# P23_MIPI_CSI1_MIPI_CSI2.net
KiCad netlist of a schematic drawn in Altium Designer
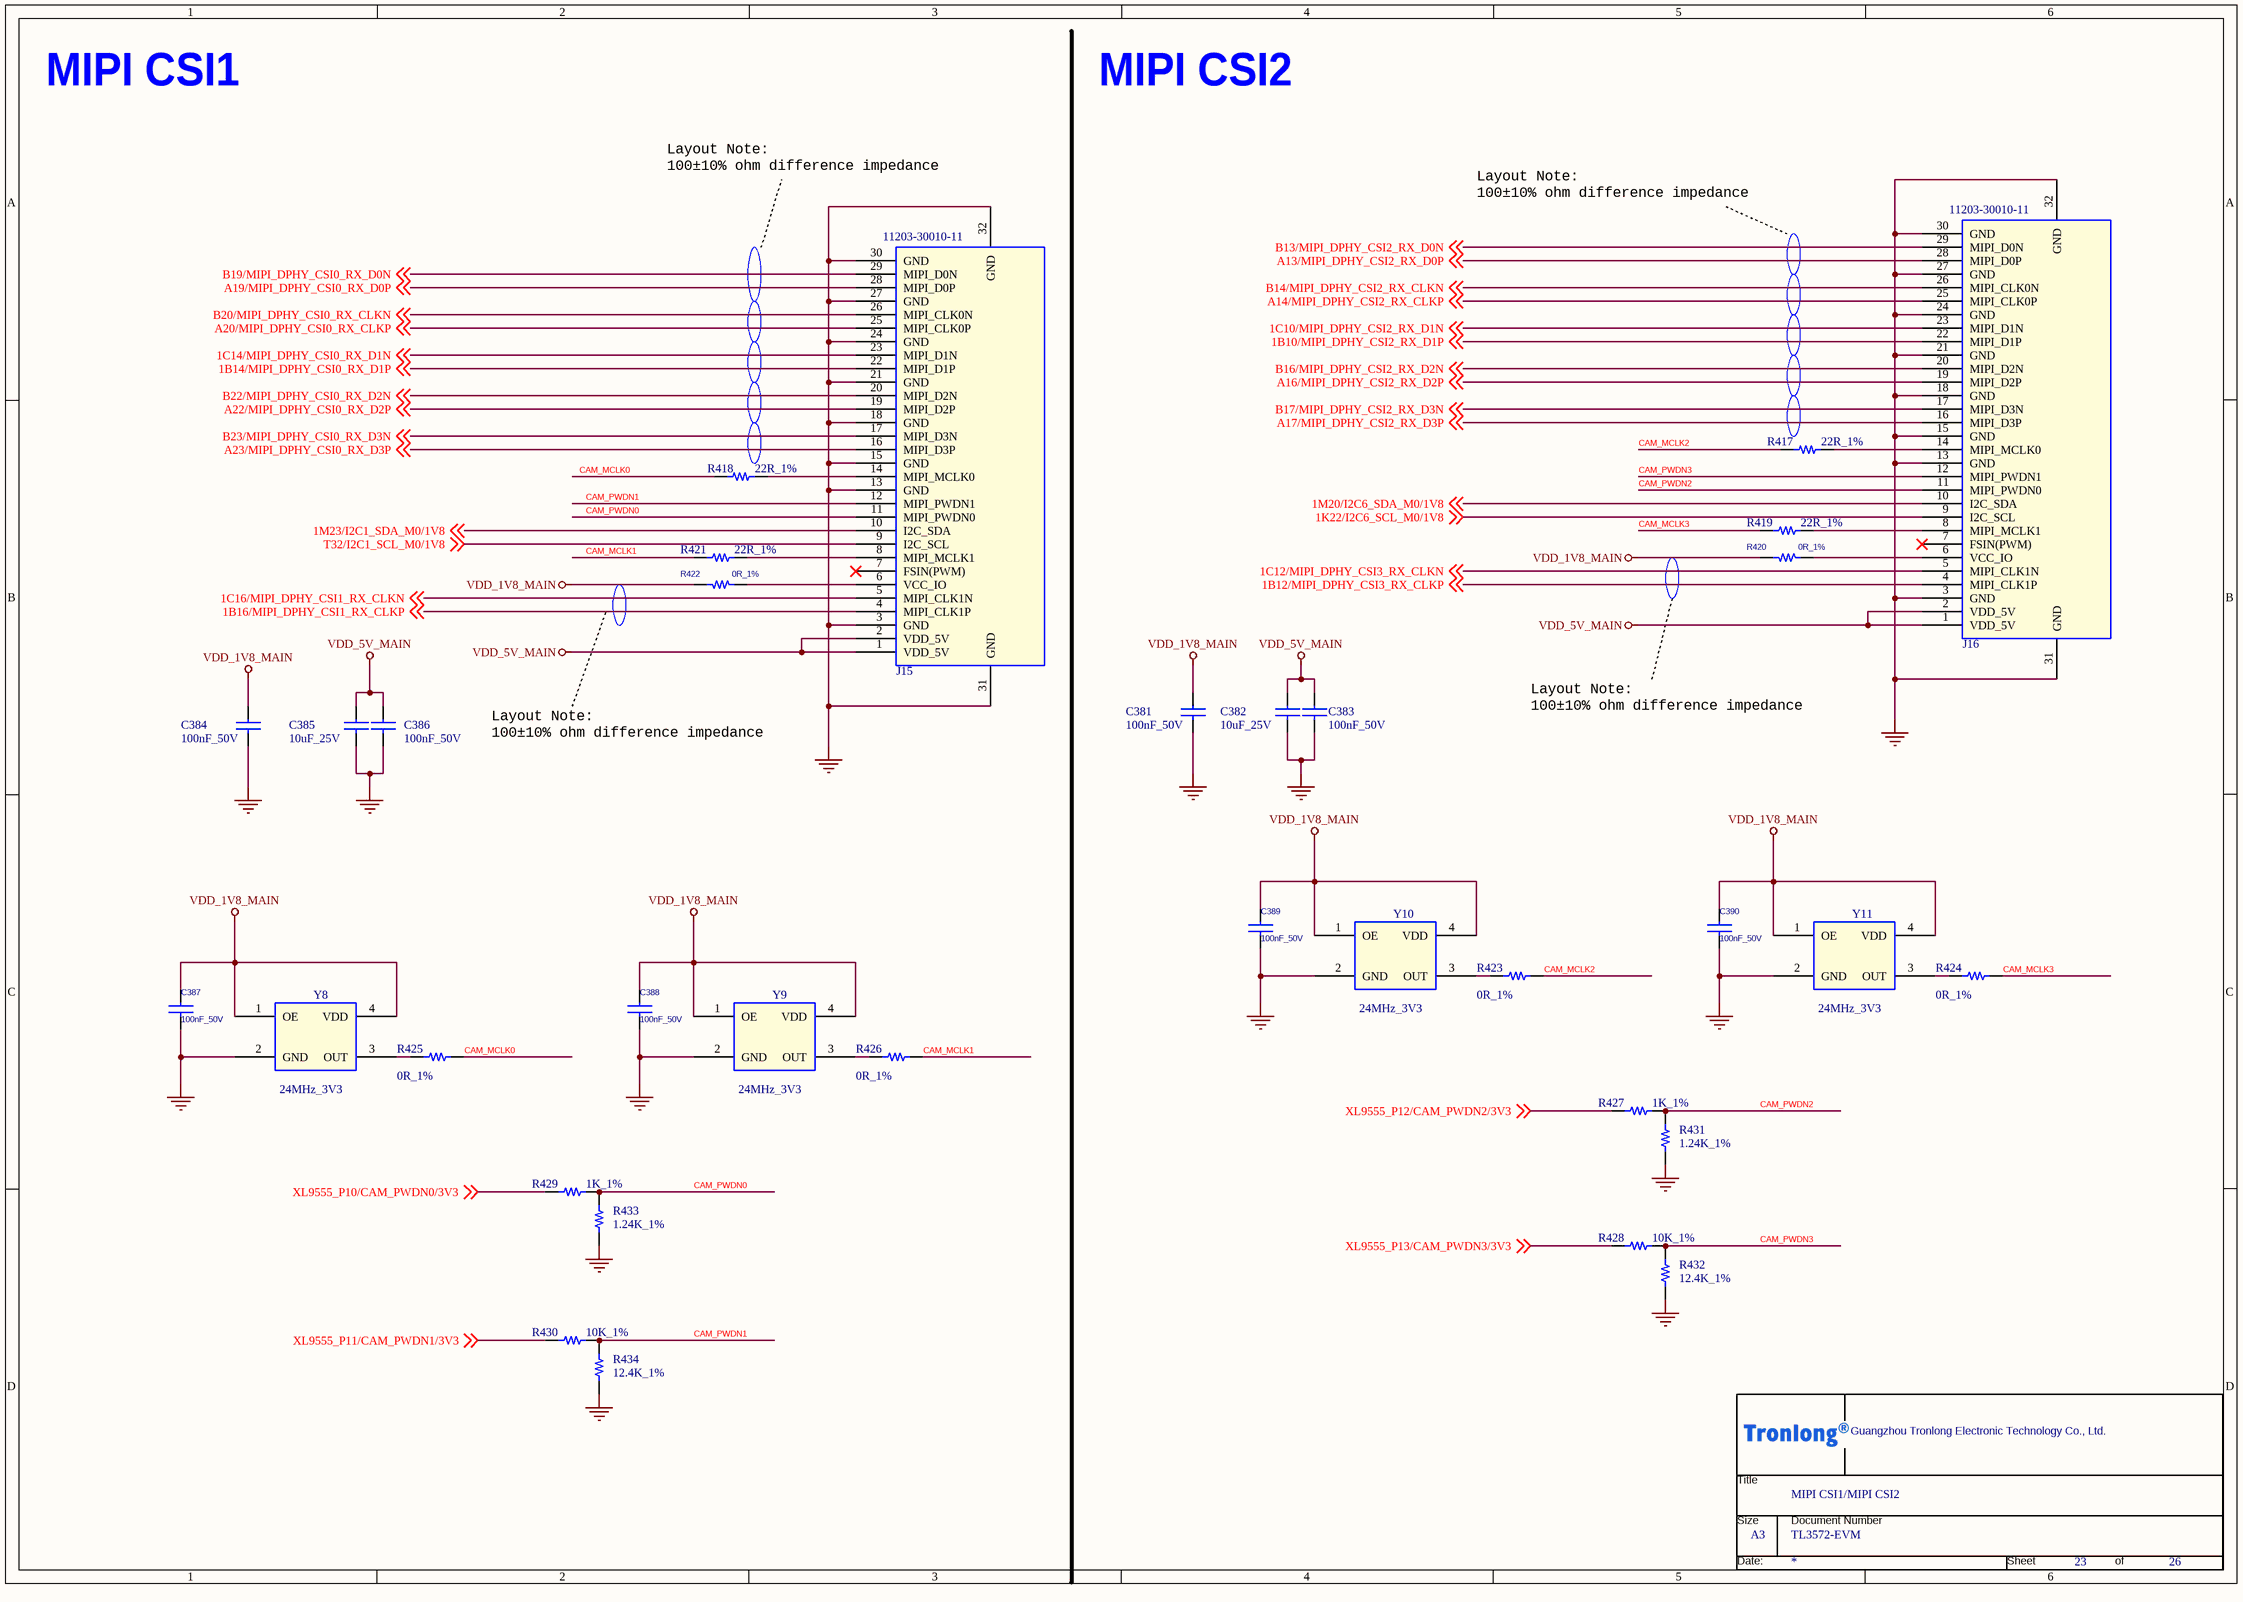
[diagram p0: P23_MIPI CSI1_MIPI CSI2.SchDoc]

(export (version "E")
  (design (tool "Eeschema 10.0.6"))
  (components
    (comp (ref "*")
      (value "TL_NEW")
      (fields
        (field (name "PAGE COUNT") "26")
        (field (name "PAGE NUMBER") "23")
        (field (name "PAGE SIZE") "A3")
        (field (name "ORGNAME") "Guangzhou Tronlong Electronic Technology Co., Ltd.")
        (field (name "TITLE") "MIPI CSI1/MIPI CSI2")
        (field (name "DOC") "TL3572-EVM")
      )
      (libsource (lib "*") (part "TL_NEW"))
    )
    (comp (ref "C381")
      (value "100nF_50V")
      (footprint "C0402")
      (description "贴片陶瓷电容,100nF,10%,50V,X7R")
      (fields
        (field (name "MANUFACTURER") "广东风华高新科技股份有限公司（FH）")
        (field (name "MANUFACTURER PARTNUMBER") "0402B104K500NT")
      )
      (libsource (lib "*") (part "CAP NP_Dup2"))
    )
    (comp (ref "C382")
      (value "10uF_25V")
      (footprint "C0603")
      (description "贴片陶瓷电容,10uF,20%,25V,X5R")
      (fields
        (field (name "MANUFACTURER") "广东风华高新科技股份有限公司（FH）")
        (field (name "MANUFACTURER PARTNUMBER") "0603X106M250NT")
      )
      (libsource (lib "*") (part "CAP NP_Dup2"))
    )
    (comp (ref "C383")
      (value "100nF_50V")
      (footprint "C0402")
      (description "贴片陶瓷电容,100nF,10%,50V,X7R")
      (fields
        (field (name "MANUFACTURER") "广东风华高新科技股份有限公司（FH）")
        (field (name "MANUFACTURER PARTNUMBER") "0402B104K500NT")
      )
      (libsource (lib "*") (part "CAP NP_Dup2"))
    )
    (comp (ref "C384")
      (value "100nF_50V")
      (footprint "C0402")
      (description "贴片陶瓷电容,100nF,10%,50V,X7R")
      (fields
        (field (name "MANUFACTURER") "广东风华高新科技股份有限公司（FH）")
        (field (name "MANUFACTURER PARTNUMBER") "0402B104K500NT")
      )
      (libsource (lib "*") (part "CAP NP_Dup2"))
    )
    (comp (ref "C385")
      (value "10uF_25V")
      (footprint "C0603")
      (description "贴片陶瓷电容,10uF,20%,25V,X5R")
      (fields
        (field (name "MANUFACTURER PARTNUMBER") "0603X106M250NT")
        (field (name "MANUFACTURER") "广东风华高新科技股份有限公司（FH）")
      )
      (libsource (lib "*") (part "CAP NP_Dup2"))
    )
    (comp (ref "C386")
      (value "100nF_50V")
      (footprint "C0402")
      (description "贴片陶瓷电容,100nF,10%,50V,X7R")
      (fields
        (field (name "MANUFACTURER") "广东风华高新科技股份有限公司（FH）")
        (field (name "MANUFACTURER PARTNUMBER") "0402B104K500NT")
      )
      (libsource (lib "*") (part "CAP NP_Dup2"))
    )
    (comp (ref "C387")
      (value "100nF_50V")
      (footprint "C0402")
      (description "贴片陶瓷电容,100nF,10%,50V,X7R")
      (fields
        (field (name "MANUFACTURER PARTNUMBER") "0402B104K500NT")
        (field (name "MANUFACTURER") "广东风华高新科技股份有限公司（FH）")
      )
      (libsource (lib "*") (part "CAP NP_Dup2"))
    )
    (comp (ref "C388")
      (value "100nF_50V")
      (footprint "C0402")
      (description "贴片陶瓷电容,100nF,10%,50V,X7R")
      (fields
        (field (name "MANUFACTURER PARTNUMBER") "0402B104K500NT")
        (field (name "MANUFACTURER") "广东风华高新科技股份有限公司（FH）")
      )
      (libsource (lib "*") (part "CAP NP_Dup2"))
    )
    (comp (ref "C389")
      (value "100nF_50V")
      (footprint "C0402")
      (description "贴片陶瓷电容,100nF,10%,50V,X7R")
      (fields
        (field (name "MANUFACTURER PARTNUMBER") "0402B104K500NT")
        (field (name "MANUFACTURER") "广东风华高新科技股份有限公司（FH）")
      )
      (libsource (lib "*") (part "CAP NP_Dup2"))
    )
    (comp (ref "C390")
      (value "100nF_50V")
      (footprint "C0402")
      (description "贴片陶瓷电容,100nF,10%,50V,X7R")
      (fields
        (field (name "MANUFACTURER PARTNUMBER") "0402B104K500NT")
        (field (name "MANUFACTURER") "广东风华高新科技股份有限公司（FH）")
      )
      (libsource (lib "*") (part "CAP NP_Dup2"))
    )
    (comp (ref "J15")
      (value "11203-30010-11")
      (footprint "CON_FFC_0D5_30P")
      (description "FFC座,30P,0.5mm间距,翻盖下接式,H=2.0mm")
      (fields (field (name "MANUFACTURER") "深圳市联畅精密电子有限公司(LCP)"))
      (libsource (lib "*") (part "30PIN FPC CON_2"))
    )
    (comp (ref "J16")
      (value "11203-30010-11")
      (footprint "CON_FFC_0D5_30P")
      (description "FFC座,30P,0.5mm间距,翻盖下接式,H=2.0mm")
      (fields (field (name "MANUFACTURER") "深圳市联畅精密电子有限公司(LCP)"))
      (libsource (lib "*") (part "30PIN FPC CON_2"))
    )
    (comp (ref "R417")
      (value "22R_1%")
      (footprint "R0402")
      (description "贴片电阻,22R,±1%,1/16W")
      (fields (field (name "MANUFACTURER PARTNUMBER") "RC-02K22R0FT") (field (name "TOLERANCE") "5%"))
      (libsource (lib "*") (part "Resistor_Dup3"))
    )
    (comp (ref "R418")
      (value "22R_1%")
      (footprint "R0402")
      (description "贴片电阻,22R,±1%,1/16W")
      (fields (field (name "MANUFACTURER PARTNUMBER") "RC-02K22R0FT") (field (name "TOLERANCE") "5%"))
      (libsource (lib "*") (part "Resistor_Dup3"))
    )
    (comp (ref "R419")
      (value "22R_1%")
      (footprint "R0402")
      (description "贴片电阻,22R,±1%,1/16W")
      (fields (field (name "MANUFACTURER PARTNUMBER") "RC-02K22R0FT") (field (name "TOLERANCE") "5%"))
      (libsource (lib "*") (part "Resistor_Dup3"))
    )
    (comp (ref "R420")
      (value "0R_1%")
      (footprint "R0402")
      (description "贴片电阻,0R,±1%,1/16W")
      (fields
        (field (name "MANUFACTURER") "广东风华高新科技股份有限公司（FH）")
        (field (name "MANUFACTURER PARTNUMBER") "RC-02000FT")
      )
      (libsource (lib "*") (part "Resistor_Dup3"))
    )
    (comp (ref "R421")
      (value "22R_1%")
      (footprint "R0402")
      (description "贴片电阻,22R,±1%,1/16W")
      (fields (field (name "MANUFACTURER") "广东风华高新科技股份有限公司（FH）") (field (name "TOLERANCE") "5%"))
      (libsource (lib "*") (part "Resistor_Dup3"))
    )
    (comp (ref "R422")
      (value "0R_1%")
      (footprint "R0402")
      (description "贴片电阻,0R,±1%,1/16W")
      (fields
        (field (name "MANUFACTURER PARTNUMBER") "RC-02000FT")
        (field (name "MANUFACTURER") "广东风华高新科技股份有限公司（FH）")
      )
      (libsource (lib "*") (part "Resistor_Dup3"))
    )
    (comp (ref "R423")
      (value "0R_1%")
      (footprint "R0603")
      (description "贴片电阻,0R,±1%,1/10W")
      (fields
        (field (name "MANUFACTURER") "广东风华高新科技股份有限公司（FH）")
        (field (name "MANUFACTURER PARTNUMBER") "RS-03000FT")
      )
      (libsource (lib "*") (part "Resistor_Dup3"))
    )
    (comp (ref "R424")
      (value "0R_1%")
      (footprint "R0603")
      (description "贴片电阻,0R,±1%,1/10W")
      (fields
        (field (name "MANUFACTURER PARTNUMBER") "RS-03000FT")
        (field (name "MANUFACTURER") "广东风华高新科技股份有限公司（FH）")
      )
      (libsource (lib "*") (part "Resistor_Dup3"))
    )
    (comp (ref "R425")
      (value "0R_1%")
      (footprint "R0603")
      (description "贴片电阻,0R,±1%,1/10W")
      (fields
        (field (name "MANUFACTURER") "广东风华高新科技股份有限公司（FH）")
        (field (name "MANUFACTURER PARTNUMBER") "RS-03000FT")
      )
      (libsource (lib "*") (part "Resistor_Dup3"))
    )
    (comp (ref "R426")
      (value "0R_1%")
      (footprint "R0603")
      (description "贴片电阻,0R,±1%,1/10W")
      (fields
        (field (name "MANUFACTURER PARTNUMBER") "RS-03000FT")
        (field (name "MANUFACTURER") "广东风华高新科技股份有限公司（FH）")
      )
      (libsource (lib "*") (part "Resistor_Dup3"))
    )
    (comp (ref "R427")
      (value "1K_1%")
      (footprint "R0402")
      (description "贴片电阻,1K,±1%,1/16W")
      (fields
        (field (name "MANUFACTURER PARTNUMBER") "RC-02K1001FT")
        (field (name "MANUFACTURER") "广东风华高新科技股份有限公司（FH）")
      )
      (libsource (lib "*") (part "Resistor_Dup3"))
    )
    (comp (ref "R428")
      (value "10K_1%")
      (footprint "R0402")
      (description "贴片电阻,10K,±1%,1/16W")
      (fields
        (field (name "MANUFACTURER") "广东风华高新科技股份有限公司（FH）")
        (field (name "MANUFACTURER PARTNUMBER") "RC-02K1002FT")
      )
      (libsource (lib "*") (part "Resistor_Dup3"))
    )
    (comp (ref "R429")
      (value "1K_1%")
      (footprint "R0402")
      (description "贴片电阻,1K,±1%,1/16W")
      (fields
        (field (name "MANUFACTURER PARTNUMBER") "RC-02K1001FT")
        (field (name "MANUFACTURER") "广东风华高新科技股份有限公司（FH）")
      )
      (libsource (lib "*") (part "Resistor_Dup3"))
    )
    (comp (ref "R430")
      (value "10K_1%")
      (footprint "R0402")
      (description "贴片电阻,10K,±1%,1/16W")
      (fields
        (field (name "MANUFACTURER PARTNUMBER") "RC-02K1002FT")
        (field (name "MANUFACTURER") "广东风华高新科技股份有限公司（FH）")
      )
      (libsource (lib "*") (part "Resistor_Dup3"))
    )
    (comp (ref "R431")
      (value "1.24K_1%")
      (footprint "R0402")
      (description "贴片电阻,1.24K,±1%,1/16W")
      (fields
        (field (name "MANUFACTURER PARTNUMBER") "RC-02K1241FT")
        (field (name "MANUFACTURER") "广东风华高新科技股份有限公司（FH）")
      )
      (libsource (lib "*") (part "Resistor_Dup3"))
    )
    (comp (ref "R432")
      (value "12.4K_1%")
      (footprint "R0402")
      (description "0402WGF1242TCE")
      (fields
        (field (name "MANUFACTURER PARTNUMBER") "12.4K,±1%,R0402,≥1/16W")
        (field (name "MANUFACTURER") "广州创龙")
      )
      (libsource (lib "*") (part "Resistor_Dup3"))
    )
    (comp (ref "R433")
      (value "1.24K_1%")
      (footprint "R0402")
      (description "贴片电阻,1.24K,±1%,1/16W")
      (fields
        (field (name "MANUFACTURER PARTNUMBER") "RC-02K1241FT")
        (field (name "MANUFACTURER") "广东风华高新科技股份有限公司（FH）")
      )
      (libsource (lib "*") (part "Resistor_Dup3"))
    )
    (comp (ref "R434")
      (value "12.4K_1%")
      (footprint "R0402")
      (description "0402WGF1242TCE")
      (fields
        (field (name "MANUFACTURER PARTNUMBER") "12.4K,±1%,R0402,≥1/16W")
        (field (name "MANUFACTURER") "广州创龙")
      )
      (libsource (lib "*") (part "Resistor_Dup3"))
    )
    (comp (ref "Y8")
      (value "24MHz_3V3")
      (footprint "SMD_3225")
      (description "四脚有源晶振,24MHz,1.62V~3.63V,CMOS,±30ppm")
      (fields
        (field (name "MANUFACTURER") "深圳市星通时频电子有限公司（SCTF）")
        (field (name "MFR_PART_NUMBER") "S3M24.576B20F30TNN")
      )
      (libsource (lib "*") (part "CMX309"))
    )
    (comp (ref "Y9")
      (value "24MHz_3V3")
      (footprint "SMD_3225")
      (description "四脚有源晶振,24MHz,1.62V~3.63V,CMOS,±30ppm")
      (fields
        (field (name "MANUFACTURER") "深圳市星通时频电子有限公司（SCTF）")
        (field (name "MFR_PART_NUMBER") "S3M24.576B20F30TNN")
      )
      (libsource (lib "*") (part "CMX309"))
    )
    (comp (ref "Y10")
      (value "24MHz_3V3")
      (footprint "SMD_3225")
      (description "四脚有源晶振,24MHz,1.62V~3.63V,CMOS,±30ppm")
      (fields
        (field (name "MANUFACTURER") "深圳市星通时频电子有限公司（SCTF）")
        (field (name "MFR_PART_NUMBER") "S3M24.576B20F30TNN")
      )
      (libsource (lib "*") (part "CMX309"))
    )
    (comp (ref "Y11")
      (value "24MHz_3V3")
      (footprint "SMD_3225")
      (description "四脚有源晶振,24MHz,1.62V~3.63V,CMOS,±30ppm")
      (fields
        (field (name "MANUFACTURER") "深圳市星通时频电子有限公司（SCTF）")
        (field (name "MFR_PART_NUMBER") "S3M24.576B20F30TNN")
      )
      (libsource (lib "*") (part "CMX309"))
    )
  )
  (nets
    (net (code "1") (name "/CAM_MCLK0") (class "Default")
      (node (ref "R418") (pin "1") (pinfunction "1_1") (pintype "passive"))
      (node (ref "R425") (pin "2") (pinfunction "2_2") (pintype "passive"))
    )
    (net (code "2") (name "/CAM_MCLK1") (class "Default")
      (node (ref "R421") (pin "1") (pinfunction "1_1") (pintype "passive"))
      (node (ref "R426") (pin "2") (pinfunction "2_2") (pintype "passive"))
    )
    (net (code "3") (name "/CAM_MCLK2") (class "Default")
      (node (ref "R417") (pin "1") (pinfunction "1_1") (pintype "passive"))
      (node (ref "R423") (pin "2") (pinfunction "2_2") (pintype "passive"))
    )
    (net (code "4") (name "/CAM_MCLK3") (class "Default")
      (node (ref "R419") (pin "1") (pinfunction "1_1") (pintype "passive"))
      (node (ref "R424") (pin "2") (pinfunction "2_2") (pintype "passive"))
    )
    (net (code "5") (name "/CAM_PWDN0") (class "Default")
      (node (ref "J15") (pin "11") (pinfunction "MIPI_PWDN0_11") (pintype "passive"))
      (node (ref "R429") (pin "1") (pinfunction "1_1") (pintype "passive"))
      (node (ref "R433") (pin "2") (pinfunction "2_2") (pintype "passive"))
    )
    (net (code "6") (name "/CAM_PWDN1") (class "Default")
      (node (ref "J15") (pin "12") (pinfunction "MIPI_PWDN1_12") (pintype "passive"))
      (node (ref "R430") (pin "1") (pinfunction "1_1") (pintype "passive"))
      (node (ref "R434") (pin "2") (pinfunction "2_2") (pintype "passive"))
    )
    (net (code "7") (name "/CAM_PWDN2") (class "Default")
      (node (ref "J16") (pin "11") (pinfunction "MIPI_PWDN0_11") (pintype "passive"))
      (node (ref "R427") (pin "1") (pinfunction "1_1") (pintype "passive"))
      (node (ref "R431") (pin "2") (pinfunction "2_2") (pintype "passive"))
    )
    (net (code "8") (name "/CAM_PWDN3") (class "Default")
      (node (ref "J16") (pin "12") (pinfunction "MIPI_PWDN1_12") (pintype "passive"))
      (node (ref "R428") (pin "1") (pinfunction "1_1") (pintype "passive"))
      (node (ref "R432") (pin "2") (pinfunction "2_2") (pintype "passive"))
    )
    (net (code "9") (name "1B10{slash}MIPI_DPHY_CSI2_RX_D1P") (class "Default")
      (node (ref "J16") (pin "22") (pinfunction "MIPI_D1P_22") (pintype "passive"))
    )
    (net (code "10") (name "1B12{slash}MIPI_DPHY_CSI3_RX_CLKP") (class "Default")
      (node (ref "J16") (pin "4") (pinfunction "MIPI_CLK1P_4") (pintype "passive"))
    )
    (net (code "11") (name "1B14{slash}MIPI_DPHY_CSI0_RX_D1P") (class "Default")
      (node (ref "J15") (pin "22") (pinfunction "MIPI_D1P_22") (pintype "passive"))
    )
    (net (code "12") (name "1B16{slash}MIPI_DPHY_CSI1_RX_CLKP") (class "Default")
      (node (ref "J15") (pin "4") (pinfunction "MIPI_CLK1P_4") (pintype "passive"))
    )
    (net (code "13") (name "1C10{slash}MIPI_DPHY_CSI2_RX_D1N") (class "Default")
      (node (ref "J16") (pin "23") (pinfunction "MIPI_D1N_23") (pintype "passive"))
    )
    (net (code "14") (name "1C12{slash}MIPI_DPHY_CSI3_RX_CLKN") (class "Default")
      (node (ref "J16") (pin "5") (pinfunction "MIPI_CLK1N_5") (pintype "passive"))
    )
    (net (code "15") (name "1C14{slash}MIPI_DPHY_CSI0_RX_D1N") (class "Default")
      (node (ref "J15") (pin "23") (pinfunction "MIPI_D1N_23") (pintype "passive"))
    )
    (net (code "16") (name "1C16{slash}MIPI_DPHY_CSI1_RX_CLKN") (class "Default")
      (node (ref "J15") (pin "5") (pinfunction "MIPI_CLK1N_5") (pintype "passive"))
    )
    (net (code "17") (name "1K22{slash}I2C6_SCL_M0{slash}1V8") (class "Default")
      (node (ref "J16") (pin "9") (pinfunction "I2C_SCL_9") (pintype "passive"))
    )
    (net (code "18") (name "1M20{slash}I2C6_SDA_M0{slash}1V8") (class "Default")
      (node (ref "J16") (pin "10") (pinfunction "I2C_SDA_10") (pintype "passive"))
    )
    (net (code "19") (name "1M23{slash}I2C1_SDA_M0{slash}1V8") (class "Default")
      (node (ref "J15") (pin "10") (pinfunction "I2C_SDA_10") (pintype "passive"))
    )
    (net (code "20") (name "A13{slash}MIPI_DPHY_CSI2_RX_D0P") (class "Default")
      (node (ref "J16") (pin "28") (pinfunction "MIPI_D0P_28") (pintype "passive"))
    )
    (net (code "21") (name "A14{slash}MIPI_DPHY_CSI2_RX_CLKP") (class "Default")
      (node (ref "J16") (pin "25") (pinfunction "MIPI_CLK0P_25") (pintype "passive"))
    )
    (net (code "22") (name "A16{slash}MIPI_DPHY_CSI2_RX_D2P") (class "Default")
      (node (ref "J16") (pin "19") (pinfunction "MIPI_D2P_19") (pintype "passive"))
    )
    (net (code "23") (name "A17{slash}MIPI_DPHY_CSI2_RX_D3P") (class "Default")
      (node (ref "J16") (pin "16") (pinfunction "MIPI_D3P_16") (pintype "passive"))
    )
    (net (code "24") (name "A19{slash}MIPI_DPHY_CSI0_RX_D0P") (class "Default")
      (node (ref "J15") (pin "28") (pinfunction "MIPI_D0P_28") (pintype "passive"))
    )
    (net (code "25") (name "A20{slash}MIPI_DPHY_CSI0_RX_CLKP") (class "Default")
      (node (ref "J15") (pin "25") (pinfunction "MIPI_CLK0P_25") (pintype "passive"))
    )
    (net (code "26") (name "A22{slash}MIPI_DPHY_CSI0_RX_D2P") (class "Default")
      (node (ref "J15") (pin "19") (pinfunction "MIPI_D2P_19") (pintype "passive"))
    )
    (net (code "27") (name "A23{slash}MIPI_DPHY_CSI0_RX_D3P") (class "Default")
      (node (ref "J15") (pin "16") (pinfunction "MIPI_D3P_16") (pintype "passive"))
    )
    (net (code "28") (name "B13{slash}MIPI_DPHY_CSI2_RX_D0N") (class "Default")
      (node (ref "J16") (pin "29") (pinfunction "MIPI_D0N_29") (pintype "passive"))
    )
    (net (code "29") (name "B14{slash}MIPI_DPHY_CSI2_RX_CLKN") (class "Default")
      (node (ref "J16") (pin "26") (pinfunction "MIPI_CLK0N_26") (pintype "passive"))
    )
    (net (code "30") (name "B16{slash}MIPI_DPHY_CSI2_RX_D2N") (class "Default")
      (node (ref "J16") (pin "20") (pinfunction "MIPI_D2N_20") (pintype "passive"))
    )
    (net (code "31") (name "B17{slash}MIPI_DPHY_CSI2_RX_D3N") (class "Default")
      (node (ref "J16") (pin "17") (pinfunction "MIPI_D3N_17") (pintype "passive"))
    )
    (net (code "32") (name "B19{slash}MIPI_DPHY_CSI0_RX_D0N") (class "Default")
      (node (ref "J15") (pin "29") (pinfunction "MIPI_D0N_29") (pintype "passive"))
    )
    (net (code "33") (name "B20{slash}MIPI_DPHY_CSI0_RX_CLKN") (class "Default")
      (node (ref "J15") (pin "26") (pinfunction "MIPI_CLK0N_26") (pintype "passive"))
    )
    (net (code "34") (name "B22{slash}MIPI_DPHY_CSI0_RX_D2N") (class "Default")
      (node (ref "J15") (pin "20") (pinfunction "MIPI_D2N_20") (pintype "passive"))
    )
    (net (code "35") (name "B23{slash}MIPI_DPHY_CSI0_RX_D3N") (class "Default")
      (node (ref "J15") (pin "17") (pinfunction "MIPI_D3N_17") (pintype "passive"))
    )
    (net (code "36") (name "GND") (class "Default")
      (node (ref "C381") (pin "2") (pinfunction "2_2") (pintype "passive"))
      (node (ref "C382") (pin "2") (pinfunction "2_2") (pintype "passive"))
      (node (ref "C383") (pin "2") (pinfunction "2_2") (pintype "passive"))
      (node (ref "C384") (pin "2") (pinfunction "2_2") (pintype "passive"))
      (node (ref "C385") (pin "2") (pinfunction "2_2") (pintype "passive"))
      (node (ref "C386") (pin "2") (pinfunction "2_2") (pintype "passive"))
      (node (ref "C387") (pin "2") (pinfunction "2_2") (pintype "passive"))
      (node (ref "C388") (pin "2") (pinfunction "2_2") (pintype "passive"))
      (node (ref "C389") (pin "2") (pinfunction "2_2") (pintype "passive"))
      (node (ref "C390") (pin "2") (pinfunction "2_2") (pintype "passive"))
      (node (ref "J15") (pin "13") (pinfunction "GND_13") (pintype "power_in"))
      (node (ref "J15") (pin "15") (pinfunction "GND_15") (pintype "power_in"))
      (node (ref "J15") (pin "18") (pinfunction "GND_18") (pintype "power_in"))
      (node (ref "J15") (pin "21") (pinfunction "GND_21") (pintype "power_in"))
      (node (ref "J15") (pin "24") (pinfunction "GND_24") (pintype "power_in"))
      (node (ref "J15") (pin "27") (pinfunction "GND_27") (pintype "power_in"))
      (node (ref "J15") (pin "3") (pinfunction "GND_3") (pintype "power_in"))
      (node (ref "J15") (pin "30") (pinfunction "GND_30") (pintype "power_in"))
      (node (ref "J15") (pin "31") (pinfunction "GND_31") (pintype "power_in"))
      (node (ref "J15") (pin "32") (pinfunction "GND_32") (pintype "power_in"))
      (node (ref "J16") (pin "13") (pinfunction "GND_13") (pintype "power_in"))
      (node (ref "J16") (pin "15") (pinfunction "GND_15") (pintype "power_in"))
      (node (ref "J16") (pin "18") (pinfunction "GND_18") (pintype "power_in"))
      (node (ref "J16") (pin "21") (pinfunction "GND_21") (pintype "power_in"))
      (node (ref "J16") (pin "24") (pinfunction "GND_24") (pintype "power_in"))
      (node (ref "J16") (pin "27") (pinfunction "GND_27") (pintype "power_in"))
      (node (ref "J16") (pin "3") (pinfunction "GND_3") (pintype "power_in"))
      (node (ref "J16") (pin "30") (pinfunction "GND_30") (pintype "power_in"))
      (node (ref "J16") (pin "31") (pinfunction "GND_31") (pintype "power_in"))
      (node (ref "J16") (pin "32") (pinfunction "GND_32") (pintype "power_in"))
      (node (ref "R431") (pin "1") (pinfunction "1_1") (pintype "passive"))
      (node (ref "R432") (pin "1") (pinfunction "1_1") (pintype "passive"))
      (node (ref "R433") (pin "1") (pinfunction "1_1") (pintype "passive"))
      (node (ref "R434") (pin "1") (pinfunction "1_1") (pintype "passive"))
      (node (ref "Y10") (pin "2") (pinfunction "GND_2") (pintype "passive"))
      (node (ref "Y11") (pin "2") (pinfunction "GND_2") (pintype "passive"))
      (node (ref "Y8") (pin "2") (pinfunction "GND_2") (pintype "passive"))
      (node (ref "Y9") (pin "2") (pinfunction "GND_2") (pintype "passive"))
    )
    (net (code "37") (name "Net-(J15-MIPI_MCLK0)") (class "Default")
      (node (ref "J15") (pin "14") (pinfunction "MIPI_MCLK0_14") (pintype "passive"))
      (node (ref "R418") (pin "2") (pinfunction "2_2") (pintype "passive"))
    )
    (net (code "38") (name "Net-(J15-MIPI_MCLK1)") (class "Default")
      (node (ref "J15") (pin "8") (pinfunction "MIPI_MCLK1_8") (pintype "passive"))
      (node (ref "R421") (pin "2") (pinfunction "2_2") (pintype "passive"))
    )
    (net (code "39") (name "Net-(J15-VCC_IO)") (class "Default")
      (node (ref "J15") (pin "6") (pinfunction "VCC_IO_6") (pintype "passive"))
      (node (ref "R422") (pin "1") (pinfunction "1_1") (pintype "passive"))
    )
    (net (code "40") (name "Net-(J16-MIPI_MCLK0)") (class "Default")
      (node (ref "J16") (pin "14") (pinfunction "MIPI_MCLK0_14") (pintype "passive"))
      (node (ref "R417") (pin "2") (pinfunction "2_2") (pintype "passive"))
    )
    (net (code "41") (name "Net-(J16-MIPI_MCLK1)") (class "Default")
      (node (ref "J16") (pin "8") (pinfunction "MIPI_MCLK1_8") (pintype "passive"))
      (node (ref "R419") (pin "2") (pinfunction "2_2") (pintype "passive"))
    )
    (net (code "42") (name "Net-(J16-VCC_IO)") (class "Default")
      (node (ref "J16") (pin "6") (pinfunction "VCC_IO_6") (pintype "passive"))
      (node (ref "R420") (pin "1") (pinfunction "1_1") (pintype "passive"))
    )
    (net (code "43") (name "Net-(Y8-OUT)") (class "Default")
      (node (ref "R425") (pin "1") (pinfunction "1_1") (pintype "passive"))
      (node (ref "Y8") (pin "3") (pinfunction "OUT_3") (pintype "passive"))
    )
    (net (code "44") (name "Net-(Y9-OUT)") (class "Default")
      (node (ref "R426") (pin "1") (pinfunction "1_1") (pintype "passive"))
      (node (ref "Y9") (pin "3") (pinfunction "OUT_3") (pintype "passive"))
    )
    (net (code "45") (name "Net-(Y10-OUT)") (class "Default")
      (node (ref "R423") (pin "1") (pinfunction "1_1") (pintype "passive"))
      (node (ref "Y10") (pin "3") (pinfunction "OUT_3") (pintype "passive"))
    )
    (net (code "46") (name "Net-(Y11-OUT)") (class "Default")
      (node (ref "R424") (pin "1") (pinfunction "1_1") (pintype "passive"))
      (node (ref "Y11") (pin "3") (pinfunction "OUT_3") (pintype "passive"))
    )
    (net (code "47") (name "T32{slash}I2C1_SCL_M0{slash}1V8") (class "Default")
      (node (ref "J15") (pin "9") (pinfunction "I2C_SCL_9") (pintype "passive"))
    )
    (net (code "48") (name "VDD_1V8_MAIN") (class "Default")
      (node (ref "C381") (pin "1") (pinfunction "1_1") (pintype "passive"))
      (node (ref "C384") (pin "1") (pinfunction "1_1") (pintype "passive"))
      (node (ref "C387") (pin "1") (pinfunction "1_1") (pintype "passive"))
      (node (ref "C388") (pin "1") (pinfunction "1_1") (pintype "passive"))
      (node (ref "C389") (pin "1") (pinfunction "1_1") (pintype "passive"))
      (node (ref "C390") (pin "1") (pinfunction "1_1") (pintype "passive"))
      (node (ref "R420") (pin "2") (pinfunction "2_2") (pintype "passive"))
      (node (ref "R422") (pin "2") (pinfunction "2_2") (pintype "passive"))
      (node (ref "Y10") (pin "1") (pinfunction "OE_1") (pintype "passive"))
      (node (ref "Y10") (pin "4") (pinfunction "VDD_4") (pintype "passive"))
      (node (ref "Y11") (pin "1") (pinfunction "OE_1") (pintype "passive"))
      (node (ref "Y11") (pin "4") (pinfunction "VDD_4") (pintype "passive"))
      (node (ref "Y8") (pin "1") (pinfunction "OE_1") (pintype "passive"))
      (node (ref "Y8") (pin "4") (pinfunction "VDD_4") (pintype "passive"))
      (node (ref "Y9") (pin "1") (pinfunction "OE_1") (pintype "passive"))
      (node (ref "Y9") (pin "4") (pinfunction "VDD_4") (pintype "passive"))
    )
    (net (code "49") (name "VDD_5V_MAIN") (class "Default")
      (node (ref "C382") (pin "1") (pinfunction "1_1") (pintype "passive"))
      (node (ref "C383") (pin "1") (pinfunction "1_1") (pintype "passive"))
      (node (ref "C385") (pin "1") (pinfunction "1_1") (pintype "passive"))
      (node (ref "C386") (pin "1") (pinfunction "1_1") (pintype "passive"))
      (node (ref "J15") (pin "1") (pinfunction "VDD_5V_1") (pintype "power_in"))
      (node (ref "J15") (pin "2") (pinfunction "VDD_5V_2") (pintype "power_in"))
      (node (ref "J16") (pin "1") (pinfunction "VDD_5V_1") (pintype "power_in"))
      (node (ref "J16") (pin "2") (pinfunction "VDD_5V_2") (pintype "power_in"))
    )
    (net (code "50") (name "XL9555_P10{slash}CAM_PWDN0{slash}3V3") (class "Default")
      (node (ref "R429") (pin "2") (pinfunction "2_2") (pintype "passive"))
    )
    (net (code "51") (name "XL9555_P11{slash}CAM_PWDN1{slash}3V3") (class "Default")
      (node (ref "R430") (pin "2") (pinfunction "2_2") (pintype "passive"))
    )
    (net (code "52") (name "XL9555_P12{slash}CAM_PWDN2{slash}3V3") (class "Default")
      (node (ref "R427") (pin "2") (pinfunction "2_2") (pintype "passive"))
    )
    (net (code "53") (name "XL9555_P13{slash}CAM_PWDN3{slash}3V3") (class "Default")
      (node (ref "R428") (pin "2") (pinfunction "2_2") (pintype "passive"))
    )
    (net (code "54") (name "unconnected-(J15-FSIN(PWM)-Pad7)") (class "Default")
      (node (ref "J15") (pin "7") (pinfunction "FSIN(PWM)_7") (pintype "passive+no_connect"))
    )
    (net (code "55") (name "unconnected-(J16-FSIN(PWM)-Pad7)") (class "Default")
      (node (ref "J16") (pin "7") (pinfunction "FSIN(PWM)_7") (pintype "passive+no_connect"))
    )
  )
)
